# Adafruit_DPS310.net
KiCad netlist of a schematic drawn in EAGLE
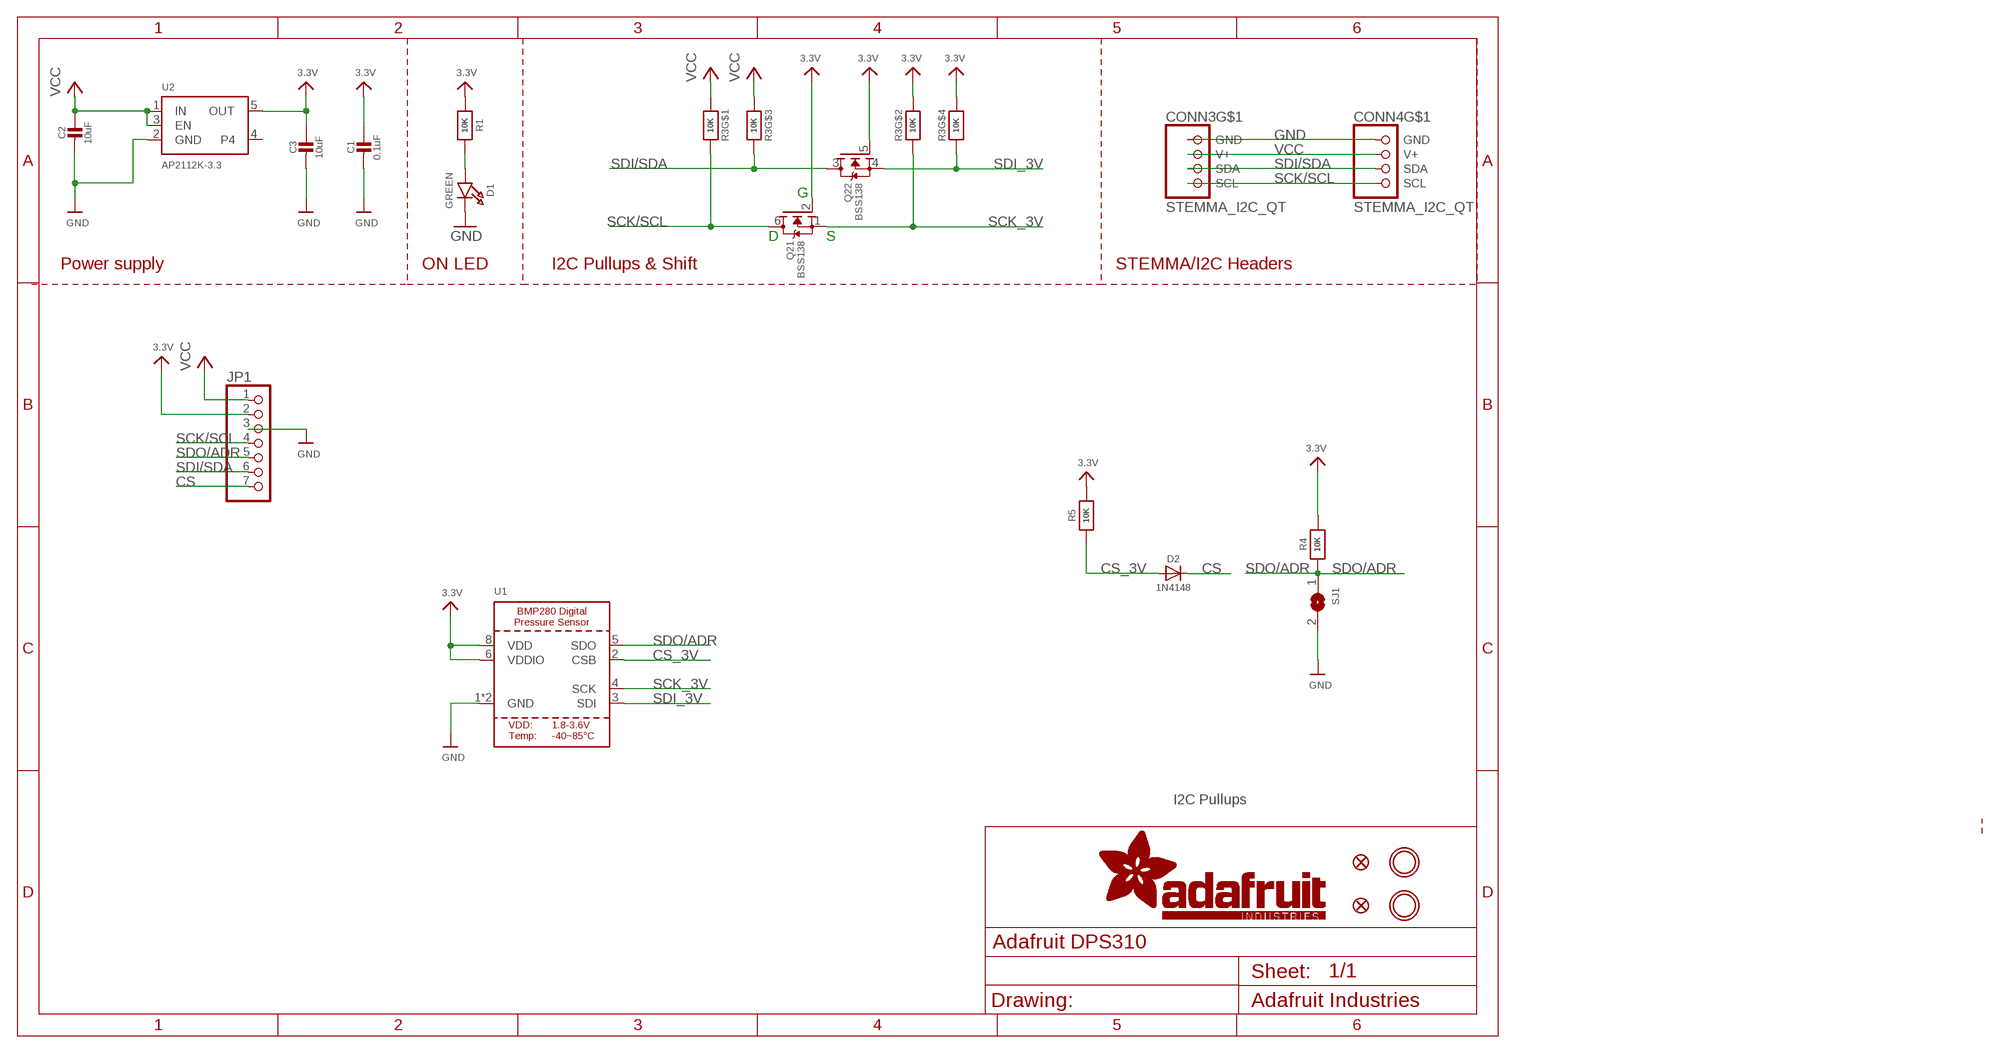
[diagram p0: schematic, sheet 1]

(export (version "E")
  (design (tool "Eeschema 10.0.6"))
  (components
    (comp (ref "C1")
      (value "0.1uF")
      (footprint "eagle-import:0603-NO")
      (libsource (lib "eagle-import") (part "CAP_CERAMIC0603_NO"))
    )
    (comp (ref "C2")
      (value "10uF")
      (footprint "eagle-import:0805-NO")
      (libsource (lib "eagle-import") (part "CAP_CERAMIC0805-NOOUTLINE"))
    )
    (comp (ref "C3")
      (value "10uF")
      (footprint "eagle-import:0805-NO")
      (libsource (lib "eagle-import") (part "CAP_CERAMIC0805-NOOUTLINE"))
    )
    (comp (ref "CONN3")
      (value "STEMMA_I2C_QT")
      (footprint "eagle-import:JST_SH4")
      (libsource (lib "eagle-import") (part "STEMMA_I2C_QT"))
    )
    (comp (ref "CONN4")
      (value "STEMMA_I2C_QT")
      (footprint "eagle-import:JST_SH4")
      (libsource (lib "eagle-import") (part "STEMMA_I2C_QT"))
    )
    (comp (ref "D1")
      (value "GREEN")
      (footprint "eagle-import:CHIPLED_0603_NOOUTLINE")
      (libsource (lib "eagle-import") (part "LED0603_NOOUTLINE"))
    )
    (comp (ref "D2")
      (value "1N4148")
      (footprint "eagle-import:SOD-323")
      (libsource (lib "eagle-import") (part "DIODESOD-323"))
    )
    (comp (ref "FID3")
      (value "FIDUCIAL_1MM")
      (footprint "eagle-import:FIDUCIAL_1MM")
      (libsource (lib "eagle-import") (part "FIDUCIAL_1MM"))
    )
    (comp (ref "FID4")
      (value "FIDUCIAL_1MM")
      (footprint "eagle-import:FIDUCIAL_1MM")
      (libsource (lib "eagle-import") (part "FIDUCIAL_1MM"))
    )
    (comp (ref "JP1")
      (value "HEADER-1X770MIL")
      (footprint "eagle-import:1X07_ROUND_70")
      (libsource (lib "eagle-import") (part "HEADER-1X770MIL"))
    )
    (comp (ref "Q2")
      (value "BSS138")
      (footprint "eagle-import:SOT363")
      (libsource (lib "eagle-import") (part "MOSFET-N_DUAL"))
    )
    (comp (ref "R1")
      (value "10K")
      (footprint "eagle-import:0603-NO")
      (libsource (lib "eagle-import") (part "RESISTOR_0603_NOOUT"))
    )
    (comp (ref "R3")
      (value "10K")
      (footprint "eagle-import:RESPACK_4X0603")
      (libsource (lib "eagle-import") (part "RESISTOR_4PACK"))
    )
    (comp (ref "R4")
      (value "10K")
      (footprint "eagle-import:0603-NO")
      (libsource (lib "eagle-import") (part "RESISTOR_0603_NOOUT"))
    )
    (comp (ref "R5")
      (value "10K")
      (footprint "eagle-import:0603-NO")
      (libsource (lib "eagle-import") (part "RESISTOR_0603_NOOUT"))
    )
    (comp (ref "SJ1")
      (value "SOLDERJUMPER")
      (footprint "eagle-import:SOLDERJUMPER_ARROW_NOPASTE")
      (libsource (lib "eagle-import") (part "SOLDERJUMPER"))
    )
    (comp (ref "U$1")
      (value "MOUNTINGHOLE2.5")
      (footprint "eagle-import:MOUNTINGHOLE_2.5_PLATED")
      (libsource (lib "eagle-import") (part "MOUNTINGHOLE2.5"))
    )
    (comp (ref "U$17")
      (value "MOUNTINGHOLE2.5")
      (footprint "eagle-import:MOUNTINGHOLE_2.5_PLATED")
      (libsource (lib "eagle-import") (part "MOUNTINGHOLE2.5"))
    )
    (comp (ref "U1")
      (value "BMP280_COMBO")
      (footprint "eagle-import:BMX280_COMBO")
      (libsource (lib "eagle-import") (part "BMP280_COMBO"))
    )
    (comp (ref "U2")
      (value "AP2112K-3.3")
      (footprint "eagle-import:SOT23-5")
      (libsource (lib "eagle-import") (part "VREG_SOT23-5"))
    )
  )
  (nets
    (net (code "1") (name "/CS") (class "Default")
      (node (ref "D2") (pin "C") (pinfunction "C_C") (pintype "passive"))
      (node (ref "JP1") (pin "7") (pinfunction "7_7") (pintype "passive"))
    )
    (net (code "2") (name "/CS_3V") (class "Default")
      (node (ref "D2") (pin "A") (pinfunction "A_A") (pintype "passive"))
      (node (ref "R5") (pin "1") (pinfunction "1_1") (pintype "passive"))
      (node (ref "U1") (pin "2") (pinfunction "CSB_2") (pintype "input"))
    )
    (net (code "3") (name "/SCK_3V") (class "Default")
      (node (ref "Q2") (pin "1") (pinfunction "S_1") (pintype "bidirectional"))
      (node (ref "R3") (pin "7") (pinfunction "2_7") (pintype "passive"))
      (node (ref "U1") (pin "4") (pinfunction "SCK_4") (pintype "input"))
    )
    (net (code "4") (name "/SCK{slash}SCL") (class "Default")
      (node (ref "CONN3") (pin "4") (pinfunction "SCL_4") (pintype "passive"))
      (node (ref "CONN4") (pin "4") (pinfunction "SCL_4") (pintype "passive"))
      (node (ref "JP1") (pin "4") (pinfunction "4_4") (pintype "passive"))
      (node (ref "Q2") (pin "6") (pinfunction "D_6") (pintype "bidirectional"))
      (node (ref "R3") (pin "8") (pinfunction "2_8") (pintype "passive"))
    )
    (net (code "5") (name "/SDI_3V") (class "Default")
      (node (ref "Q2") (pin "4") (pinfunction "S_4") (pintype "bidirectional"))
      (node (ref "R3") (pin "5") (pinfunction "2_5") (pintype "passive"))
      (node (ref "U1") (pin "3") (pinfunction "SDI_3") (pintype "input"))
    )
    (net (code "6") (name "/SDI{slash}SDA") (class "Default")
      (node (ref "CONN3") (pin "3") (pinfunction "SDA_3") (pintype "passive"))
      (node (ref "CONN4") (pin "3") (pinfunction "SDA_3") (pintype "passive"))
      (node (ref "JP1") (pin "6") (pinfunction "6_6") (pintype "passive"))
      (node (ref "Q2") (pin "3") (pinfunction "D_3") (pintype "bidirectional"))
      (node (ref "R3") (pin "6") (pinfunction "2_6") (pintype "passive"))
    )
    (net (code "7") (name "/SDO{slash}ADR") (class "Default")
      (node (ref "JP1") (pin "5") (pinfunction "5_5") (pintype "passive"))
      (node (ref "R4") (pin "1") (pinfunction "1_1") (pintype "passive"))
      (node (ref "SJ1") (pin "1") (pinfunction "1_1") (pintype "passive"))
      (node (ref "U1") (pin "5") (pinfunction "SDO_5") (pintype "output"))
    )
    (net (code "8") (name "3.3V") (class "Default")
      (node (ref "C1") (pin "1") (pinfunction "1_1") (pintype "passive"))
      (node (ref "C3") (pin "1") (pinfunction "1_1") (pintype "passive"))
      (node (ref "JP1") (pin "2") (pinfunction "2_2") (pintype "passive"))
      (node (ref "Q2") (pin "2") (pinfunction "G_2") (pintype "bidirectional"))
      (node (ref "Q2") (pin "5") (pinfunction "G_5") (pintype "bidirectional"))
      (node (ref "R1") (pin "1") (pinfunction "1_1") (pintype "passive"))
      (node (ref "R3") (pin "2") (pinfunction "1_2") (pintype "passive"))
      (node (ref "R3") (pin "4") (pinfunction "1_4") (pintype "passive"))
      (node (ref "R4") (pin "2") (pinfunction "2_2") (pintype "passive"))
      (node (ref "R5") (pin "2") (pinfunction "2_2") (pintype "passive"))
      (node (ref "U1") (pin "6") (pinfunction "VDDIO_6") (pintype "power_in"))
      (node (ref "U1") (pin "8") (pinfunction "VDD_8") (pintype "power_in"))
      (node (ref "U2") (pin "5") (pinfunction "OUT_5") (pintype "power_in"))
    )
    (net (code "9") (name "GND") (class "Default")
      (node (ref "C1") (pin "2") (pinfunction "2_2") (pintype "passive"))
      (node (ref "C2") (pin "2") (pinfunction "2_2") (pintype "passive"))
      (node (ref "C3") (pin "2") (pinfunction "2_2") (pintype "passive"))
      (node (ref "CONN3") (pin "1") (pinfunction "GND_1") (pintype "passive"))
      (node (ref "CONN4") (pin "1") (pinfunction "GND_1") (pintype "passive"))
      (node (ref "D1") (pin "C") (pinfunction "C_C") (pintype "passive"))
      (node (ref "JP1") (pin "3") (pinfunction "3_3") (pintype "passive"))
      (node (ref "SJ1") (pin "2") (pinfunction "2_2") (pintype "passive"))
      (node (ref "U1") (pin "1") (pinfunction "GND_1") (pintype "power_in"))
      (node (ref "U1") (pin "7") (pinfunction "GND_7") (pintype "power_in"))
      (node (ref "U2") (pin "2") (pinfunction "GND_2") (pintype "power_in"))
    )
    (net (code "10") (name "Net-(D1-PadA)") (class "Default")
      (node (ref "D1") (pin "A") (pinfunction "A_A") (pintype "passive"))
      (node (ref "R1") (pin "2") (pinfunction "2_2") (pintype "passive"))
    )
    (net (code "11") (name "VCC") (class "Default")
      (node (ref "C2") (pin "1") (pinfunction "1_1") (pintype "passive"))
      (node (ref "CONN3") (pin "2") (pinfunction "V+_2") (pintype "passive"))
      (node (ref "CONN4") (pin "2") (pinfunction "V+_2") (pintype "passive"))
      (node (ref "JP1") (pin "1") (pinfunction "1_1") (pintype "passive"))
      (node (ref "R3") (pin "1") (pinfunction "1_1") (pintype "passive"))
      (node (ref "R3") (pin "3") (pinfunction "1_3") (pintype "passive"))
      (node (ref "U2") (pin "1") (pinfunction "IN_1") (pintype "power_in"))
      (node (ref "U2") (pin "3") (pinfunction "EN_3") (pintype "input"))
    )
    (net (code "12") (name "unconnected-(U2-P4-Pad4)") (class "Default")
      (node (ref "U2") (pin "4") (pinfunction "P4_4") (pintype "bidirectional"))
    )
  )
)
